# ver_3.net
KiCad netlist of a schematic drawn in Altium Designer
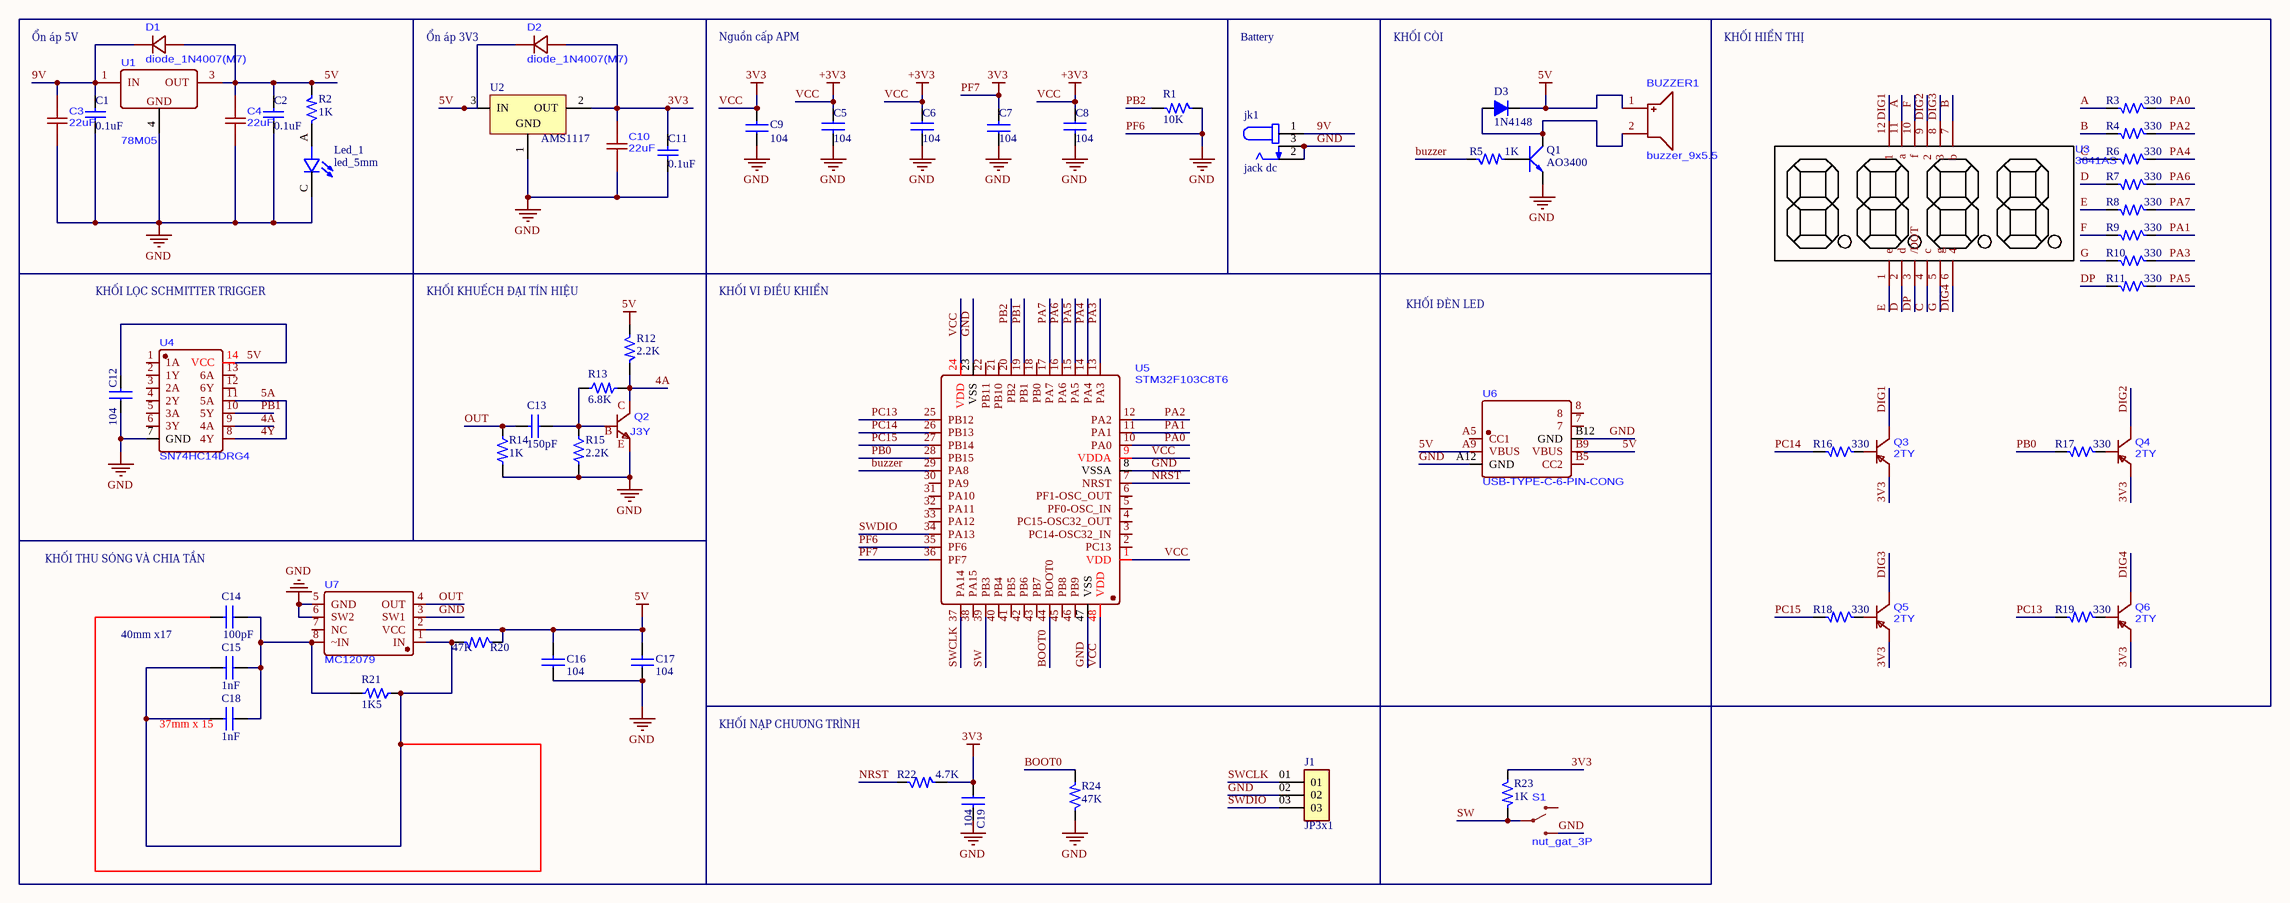
[diagram p0: ver_3.SchDoc]

(export (version "E")
  (design (tool "Eeschema 10.0.6"))
  (components
    (comp (ref "BUZZER1")
      (value "buzzer_9x5.5")
      (footprint "buzzer_9x5.5")
      (libsource (lib "Phong_Cach") (part "buzzer_9x5.5"))
    )
    (comp (ref "C1")
      (value "0.1uF")
      (footprint "CN-SMD-0603")
      (libsource (lib "Thu Vien Chuan MH") (part "CAP 104"))
    )
    (comp (ref "C2")
      (value "0.1uF")
      (footprint "CN-SMD-0603")
      (libsource (lib "Thu Vien Chuan MH") (part "CAP 104"))
    )
    (comp (ref "C3") (value "22uF") (footprint "cap_1206") (libsource (lib "Phong_Cach") (part "cap_1206")))
    (comp (ref "C4") (value "22uF") (footprint "cap_1206") (libsource (lib "Phong_Cach") (part "cap_1206")))
    (comp (ref "C5")
      (value "104")
      (footprint "CN-SMD-0603")
      (description "Tu 0805")
      (libsource (lib "BLE_ST") (part "Tu 0805_1"))
    )
    (comp (ref "C6")
      (value "104")
      (footprint "CN-SMD-0603")
      (description "Tu 0805")
      (libsource (lib "BLE_ST") (part "Tu 0805_1"))
    )
    (comp (ref "C7")
      (value "104")
      (footprint "CN-SMD-0603")
      (description "Tu 0805")
      (libsource (lib "BLE_ST") (part "Tu 0805_1"))
    )
    (comp (ref "C8")
      (value "104")
      (footprint "CN-SMD-0603")
      (description "Tu 0805")
      (libsource (lib "BLE_ST") (part "Tu 0805_1"))
    )
    (comp (ref "C9")
      (value "104")
      (footprint "CN-SMD-0603")
      (description "Tu 0805")
      (libsource (lib "BLE_ST") (part "Tu 0805_1"))
    )
    (comp (ref "C10") (value "22uF") (footprint "cap_1206") (libsource (lib "Phong_Cach") (part "cap_1206")))
    (comp (ref "C11")
      (value "0.1uF")
      (footprint "CN-SMD-0603")
      (libsource (lib "Thu Vien Chuan MH") (part "CAP 104"))
    )
    (comp (ref "C12")
      (value "104")
      (footprint "CN-SMD-0603")
      (description "Tu 0805")
      (libsource (lib "BLE_ST") (part "Tu 0805_1"))
    )
    (comp (ref "C13")
      (value "150pF")
      (footprint "CN-SMD-0603")
      (description "Tu 0805")
      (libsource (lib "BLE_ST") (part "Tu 0805_1"))
    )
    (comp (ref "C14")
      (value "100pF")
      (footprint "CN-SMD-0603")
      (description "Tu 0805")
      (libsource (lib "BLE_ST") (part "Tu 0805_1"))
    )
    (comp (ref "C15")
      (value "1nF")
      (footprint "CN-SMD-0603")
      (description "Tu 0805")
      (libsource (lib "BLE_ST") (part "Tu 0805_1"))
    )
    (comp (ref "C16")
      (value "104")
      (footprint "CN-SMD-0603")
      (description "Tu 0805")
      (libsource (lib "BLE_ST") (part "Tu 0805_1"))
    )
    (comp (ref "C17")
      (value "104")
      (footprint "CN-SMD-0603")
      (description "Tu 0805")
      (libsource (lib "BLE_ST") (part "Tu 0805_1"))
    )
    (comp (ref "C18")
      (value "1nF")
      (footprint "CN-SMD-0603")
      (description "Tu 0805")
      (libsource (lib "BLE_ST") (part "Tu 0805_1"))
    )
    (comp (ref "C19")
      (value "104")
      (footprint "CN-SMD-0603")
      (description "Tu 0805")
      (libsource (lib "BLE_ST") (part "Tu 0805_1"))
    )
    (comp (ref "D1")
      (value "diode_1N4007(M7)")
      (footprint "diode_1N4007-M7")
      (libsource (lib "Phong_Cach") (part "diode_1N4007(M7)"))
    )
    (comp (ref "D2")
      (value "diode_1N4007(M7)")
      (footprint "diode_1N4007-M7")
      (libsource (lib "Phong_Cach") (part "diode_1N4007(M7)"))
    )
    (comp (ref "D3")
      (value "1N4148")
      (footprint "SOD-123")
      (description "Diode 1A")
      (libsource (lib "syhaunguyen") (part "D1A"))
    )
    (comp (ref "J1") (value "JP3x1") (footprint "JP3x1") (libsource (lib "Phong_Cach") (part "JP3x1")))
    (comp (ref "jk1") (value "jack dc") (footprint "jack dc") (libsource (lib "Phong_Cach") (part "jack dc")))
    (comp (ref "Led_1")
      (value "led_5mm")
      (footprint "led_5mm")
      (libsource (lib "Phong_Cach") (part "led_5mm"))
    )
    (comp (ref "Q1")
      (value "AO3400")
      (footprint "SOT23B")
      (description "NPN 600mW, ECB")
      (libsource (lib "BLE_ST") (part "C1815"))
    )
    (comp (ref "Q2") (value "J3Y") (footprint "j3y") (libsource (lib "Phong_Cach") (part "S8050/J3Y/0.4")))
    (comp (ref "Q3") (value "2TY") (footprint "2TY") (libsource (lib "Phong_Cach") (part "2TY")))
    (comp (ref "Q4") (value "2TY") (footprint "2TY") (libsource (lib "Phong_Cach") (part "2TY")))
    (comp (ref "Q5") (value "2TY") (footprint "2TY") (libsource (lib "Phong_Cach") (part "2TY")))
    (comp (ref "Q6") (value "2TY") (footprint "2TY") (libsource (lib "Phong_Cach") (part "2TY")))
    (comp (ref "R1")
      (value "10K")
      (footprint "RES-SMD-0603")
      (description "Tro 0805")
      (libsource (lib "BLE_ST") (part "Tro 0805_1"))
    )
    (comp (ref "R2")
      (value "1K")
      (footprint "RES-SMD-0603")
      (description "Resistor 1/4W")
      (libsource (lib "BLE_ST") (part "Res"))
    )
    (comp (ref "R3")
      (value "330")
      (footprint "RES-SMD-0603")
      (description "Resistor 1/4W")
      (libsource (lib "BLE_ST") (part "Res"))
    )
    (comp (ref "R4")
      (value "330")
      (footprint "RES-SMD-0603")
      (description "Resistor 1/4W")
      (libsource (lib "BLE_ST") (part "Res"))
    )
    (comp (ref "R5")
      (value "1K")
      (footprint "RES-SMD-0603")
      (description "Resistor 1/4W")
      (libsource (lib "Lib_Chuan_03_08_2013") (part "Res"))
    )
    (comp (ref "R6")
      (value "330")
      (footprint "RES-SMD-0603")
      (description "Resistor 1/4W")
      (libsource (lib "BLE_ST") (part "Res"))
    )
    (comp (ref "R7")
      (value "330")
      (footprint "RES-SMD-0603")
      (description "Resistor 1/4W")
      (libsource (lib "BLE_ST") (part "Res"))
    )
    (comp (ref "R8")
      (value "330")
      (footprint "RES-SMD-0603")
      (description "Resistor 1/4W")
      (libsource (lib "BLE_ST") (part "Res"))
    )
    (comp (ref "R9")
      (value "330")
      (footprint "RES-SMD-0603")
      (description "Resistor 1/4W")
      (libsource (lib "BLE_ST") (part "Res"))
    )
    (comp (ref "R10")
      (value "330")
      (footprint "RES-SMD-0603")
      (description "Resistor 1/4W")
      (libsource (lib "BLE_ST") (part "Res"))
    )
    (comp (ref "R11")
      (value "330")
      (footprint "RES-SMD-0603")
      (description "Resistor 1/4W")
      (libsource (lib "BLE_ST") (part "Res"))
    )
    (comp (ref "R12")
      (value "2.2K")
      (footprint "RES-SMD-0603")
      (description "Tro 0805")
      (libsource (lib "BLE_ST") (part "Tro 0805_1"))
    )
    (comp (ref "R13")
      (value "6.8K")
      (footprint "RES-SMD-0603")
      (description "Tro 0805")
      (libsource (lib "BLE_ST") (part "Tro 0805_1"))
    )
    (comp (ref "R14")
      (value "1K")
      (footprint "RES-SMD-0603")
      (description "Tro 0805")
      (libsource (lib "BLE_ST") (part "Tro 0805_1"))
    )
    (comp (ref "R15")
      (value "2.2K")
      (footprint "RES-SMD-0603")
      (description "Tro 0805")
      (libsource (lib "BLE_ST") (part "Tro 0805_1"))
    )
    (comp (ref "R16")
      (value "330")
      (footprint "RES-SMD-0603")
      (description "Resistor 1/4W")
      (libsource (lib "BLE_ST") (part "Res"))
    )
    (comp (ref "R17")
      (value "330")
      (footprint "RES-SMD-0603")
      (description "Resistor 1/4W")
      (libsource (lib "BLE_ST") (part "Res"))
    )
    (comp (ref "R18")
      (value "330")
      (footprint "RES-SMD-0603")
      (description "Resistor 1/4W")
      (libsource (lib "BLE_ST") (part "Res"))
    )
    (comp (ref "R19")
      (value "330")
      (footprint "RES-SMD-0603")
      (description "Resistor 1/4W")
      (libsource (lib "BLE_ST") (part "Res"))
    )
    (comp (ref "R20")
      (value "47K")
      (footprint "RES-SMD-0603")
      (description "Tro 0805")
      (libsource (lib "BLE_ST") (part "Tro 0805_1"))
    )
    (comp (ref "R21")
      (value "1K5")
      (footprint "RES-SMD-0603")
      (description "Tro 0805")
      (libsource (lib "BLE_ST") (part "Tro 0805_1"))
    )
    (comp (ref "R22")
      (value "4.7K")
      (footprint "RES-SMD-0603")
      (description "Tro 0805")
      (libsource (lib "BLE_ST") (part "Tro 0805_1"))
    )
    (comp (ref "R23")
      (value "1K")
      (footprint "RES-SMD-0603")
      (description "Tro 0805")
      (libsource (lib "BLE_ST") (part "Tro 0805_1"))
    )
    (comp (ref "R24")
      (value "47K")
      (footprint "RES-SMD-0603")
      (description "Tro 0805")
      (libsource (lib "BLE_ST") (part "Tro 0805_1"))
    )
    (comp (ref "S1")
      (value "nut_gat_3P")
      (footprint "nut_gat_3p")
      (libsource (lib "Phong_Cach") (part "nut_gat_3P"))
    )
    (comp (ref "U1") (value "78M05") (footprint "78M05") (libsource (lib "Phong_Cach") (part "78M05")))
    (comp (ref "U2")
      (value "AMS1117")
      (footprint "AMS1117-SOT223")
      (libsource (lib "QT TECH CO.,LTD") (part "AMS1117"))
    )
    (comp (ref "U3") (value "3641AS") (footprint "3641BS") (libsource (lib "Phong_Cach") (part "3641AS")))
    (comp (ref "U4")
      (value "SN74HC14DRG4")
      (footprint "74HC14")
      (libsource (lib "Phong_Cach") (part "SN74HC14DRG4"))
    )
    (comp (ref "U5")
      (value "STM32F103C8T6")
      (footprint "LQFP-48_L7.0-W7.0-P0.50-LS9.0-BL")
      (libsource (lib "Phong_Cach") (part "APM32F030C8T6"))
    )
    (comp (ref "U6")
      (value "USB-TYPE-C-6-PIN-CONG")
      (footprint "USB-TYPE-C-6-PIN-CONG")
      (libsource (lib "Phong_Cach") (part "USB-TYPE-C-6-PIN-CONG"))
    )
    (comp (ref "U7") (value "MC12079") (footprint "MC12079") (libsource (lib "Phong_Cach") (part "MC12079")))
  )
  (nets
    (net (code "1") (name "+3V3") (class "Default")
      (node (ref "C10") (pin "2") (pinfunction "2_2") (pintype "passive"))
      (node (ref "C11") (pin "2") (pinfunction "2_2") (pintype "passive"))
      (node (ref "C19") (pin "1") (pinfunction "1_1") (pintype "passive"))
      (node (ref "C5") (pin "1") (pinfunction "1_1") (pintype "passive"))
      (node (ref "C6") (pin "1") (pinfunction "1_1") (pintype "passive"))
      (node (ref "C7") (pin "2") (pinfunction "2_2") (pintype "passive"))
      (node (ref "C8") (pin "1") (pinfunction "1_1") (pintype "passive"))
      (node (ref "C9") (pin "2") (pinfunction "2_2") (pintype "passive"))
      (node (ref "D2") (pin "2") (pinfunction "A_2") (pintype "passive"))
      (node (ref "Q3") (pin "2") (pinfunction "E_2") (pintype "passive"))
      (node (ref "Q4") (pin "2") (pinfunction "E_2") (pintype "passive"))
      (node (ref "Q5") (pin "2") (pinfunction "E_2") (pintype "passive"))
      (node (ref "Q6") (pin "2") (pinfunction "E_2") (pintype "passive"))
      (node (ref "R22") (pin "2") (pinfunction "2_2") (pintype "passive"))
      (node (ref "R23") (pin "1") (pinfunction "1_1") (pintype "passive"))
      (node (ref "U2") (pin "2") (pinfunction "OUT_2") (pintype "power_in"))
      (node (ref "U5") (pin "1") (pinfunction "VDD_1") (pintype "passive"))
      (node (ref "U5") (pin "24") (pinfunction "VDD_24") (pintype "passive"))
      (node (ref "U5") (pin "36") (pinfunction "PF7_36") (pintype "passive"))
      (node (ref "U5") (pin "48") (pinfunction "VDD_48") (pintype "passive"))
      (node (ref "U5") (pin "9") (pinfunction "VDDA_9") (pintype "passive"))
    )
    (net (code "2") (name "/4A") (class "Default")
      (node (ref "Q2") (pin "3") (pinfunction "C_3") (pintype "passive"))
      (node (ref "R12") (pin "2") (pinfunction "2_2") (pintype "passive"))
      (node (ref "R13") (pin "2") (pinfunction "2_2") (pintype "passive"))
      (node (ref "U4") (pin "9") (pinfunction "4A_9") (pintype "passive"))
    )
    (net (code "3") (name "/4Y") (class "Default")
      (node (ref "U4") (pin "11") (pinfunction "5A_11") (pintype "passive"))
      (node (ref "U4") (pin "8") (pinfunction "4Y_8") (pintype "passive"))
    )
    (net (code "4") (name "/9V") (class "Default")
      (node (ref "C1") (pin "2") (pinfunction "2_2") (pintype "passive"))
      (node (ref "C3") (pin "2") (pinfunction "2_2") (pintype "passive"))
      (node (ref "D1") (pin "1") (pinfunction "K_1") (pintype "passive"))
      (node (ref "U1") (pin "1") (pinfunction "IN_1") (pintype "passive"))
      (node (ref "jk1") (pin "1") (pinfunction "1_1") (pintype "passive"))
    )
    (net (code "5") (name "/A") (class "Default")
      (node (ref "R3") (pin "2") (pinfunction "2_2") (pintype "passive"))
      (node (ref "U3") (pin "11") (pinfunction "a_11") (pintype "passive"))
    )
    (net (code "6") (name "/B") (class "Default")
      (node (ref "R4") (pin "2") (pinfunction "2_2") (pintype "passive"))
      (node (ref "U3") (pin "7") (pinfunction "b_7") (pintype "passive"))
    )
    (net (code "7") (name "/BOOT0") (class "Default")
      (node (ref "R24") (pin "2") (pinfunction "2_2") (pintype "passive"))
      (node (ref "U5") (pin "44") (pinfunction "BOOT0_44") (pintype "passive"))
    )
    (net (code "8") (name "/C") (class "Default")
      (node (ref "R6") (pin "2") (pinfunction "2_2") (pintype "passive"))
      (node (ref "U3") (pin "4") (pinfunction "c_4") (pintype "passive"))
    )
    (net (code "9") (name "/D") (class "Default")
      (node (ref "R7") (pin "2") (pinfunction "2_2") (pintype "passive"))
      (node (ref "U3") (pin "2") (pinfunction "d_2") (pintype "passive"))
    )
    (net (code "10") (name "/DIG1") (class "Default")
      (node (ref "Q3") (pin "3") (pinfunction "C_3") (pintype "passive"))
      (node (ref "U3") (pin "12") (pinfunction "1_12") (pintype "passive"))
    )
    (net (code "11") (name "/DIG2") (class "Default")
      (node (ref "Q4") (pin "3") (pinfunction "C_3") (pintype "passive"))
      (node (ref "U3") (pin "9") (pinfunction "2_9") (pintype "passive"))
    )
    (net (code "12") (name "/DIG3") (class "Default")
      (node (ref "Q5") (pin "3") (pinfunction "C_3") (pintype "passive"))
      (node (ref "U3") (pin "8") (pinfunction "3_8") (pintype "passive"))
    )
    (net (code "13") (name "/DIG4") (class "Default")
      (node (ref "Q6") (pin "3") (pinfunction "C_3") (pintype "passive"))
      (node (ref "U3") (pin "6") (pinfunction "4_6") (pintype "passive"))
    )
    (net (code "14") (name "/DP") (class "Default")
      (node (ref "R11") (pin "2") (pinfunction "2_2") (pintype "passive"))
      (node (ref "U3") (pin "3") (pinfunction "/DOT_3") (pintype "passive"))
    )
    (net (code "15") (name "/E") (class "Default")
      (node (ref "R8") (pin "2") (pinfunction "2_2") (pintype "passive"))
      (node (ref "U3") (pin "1") (pinfunction "e_1") (pintype "passive"))
    )
    (net (code "16") (name "/F") (class "Default")
      (node (ref "R9") (pin "2") (pinfunction "2_2") (pintype "passive"))
      (node (ref "U3") (pin "10") (pinfunction "f_10") (pintype "passive"))
    )
    (net (code "17") (name "/G") (class "Default")
      (node (ref "R10") (pin "2") (pinfunction "2_2") (pintype "passive"))
      (node (ref "U3") (pin "5") (pinfunction "g_5") (pintype "passive"))
    )
    (net (code "18") (name "/NRST") (class "Default")
      (node (ref "R22") (pin "1") (pinfunction "1_1") (pintype "passive"))
      (node (ref "U5") (pin "7") (pinfunction "NRST_7") (pintype "passive"))
    )
    (net (code "19") (name "/OUT") (class "Default")
      (node (ref "C13") (pin "2") (pinfunction "2_2") (pintype "passive"))
      (node (ref "R14") (pin "1") (pinfunction "1_1") (pintype "passive"))
      (node (ref "U7") (pin "4") (pinfunction "OUT_4") (pintype "passive"))
    )
    (net (code "20") (name "/PA0") (class "Default")
      (node (ref "R3") (pin "1") (pinfunction "1_1") (pintype "passive"))
      (node (ref "U5") (pin "10") (pinfunction "PA0_10") (pintype "passive"))
    )
    (net (code "21") (name "/PA1") (class "Default")
      (node (ref "R9") (pin "1") (pinfunction "1_1") (pintype "passive"))
      (node (ref "U5") (pin "11") (pinfunction "PA1_11") (pintype "passive"))
    )
    (net (code "22") (name "/PA2") (class "Default")
      (node (ref "R4") (pin "1") (pinfunction "1_1") (pintype "passive"))
      (node (ref "U5") (pin "12") (pinfunction "PA2_12") (pintype "passive"))
    )
    (net (code "23") (name "/PA3") (class "Default")
      (node (ref "R10") (pin "1") (pinfunction "1_1") (pintype "passive"))
      (node (ref "U5") (pin "13") (pinfunction "PA3_13") (pintype "passive"))
    )
    (net (code "24") (name "/PA4") (class "Default")
      (node (ref "R6") (pin "1") (pinfunction "1_1") (pintype "passive"))
      (node (ref "U5") (pin "14") (pinfunction "PA4_14") (pintype "passive"))
    )
    (net (code "25") (name "/PA5") (class "Default")
      (node (ref "R11") (pin "1") (pinfunction "1_1") (pintype "passive"))
      (node (ref "U5") (pin "15") (pinfunction "PA5_15") (pintype "passive"))
    )
    (net (code "26") (name "/PA6") (class "Default")
      (node (ref "R7") (pin "1") (pinfunction "1_1") (pintype "passive"))
      (node (ref "U5") (pin "16") (pinfunction "PA6_16") (pintype "passive"))
    )
    (net (code "27") (name "/PA7") (class "Default")
      (node (ref "R8") (pin "1") (pinfunction "1_1") (pintype "passive"))
      (node (ref "U5") (pin "17") (pinfunction "PA7_17") (pintype "passive"))
    )
    (net (code "28") (name "/PB0") (class "Default")
      (node (ref "R17") (pin "2") (pinfunction "2_2") (pintype "passive"))
      (node (ref "U5") (pin "28") (pinfunction "PB15_28") (pintype "passive"))
    )
    (net (code "29") (name "/PB1") (class "Default")
      (node (ref "U4") (pin "10") (pinfunction "5Y_10") (pintype "passive"))
      (node (ref "U5") (pin "19") (pinfunction "PB1_19") (pintype "passive"))
    )
    (net (code "30") (name "/PB2") (class "Default")
      (node (ref "R1") (pin "2") (pinfunction "2_2") (pintype "passive"))
      (node (ref "U5") (pin "20") (pinfunction "PB2_20") (pintype "passive"))
    )
    (net (code "31") (name "/PC13") (class "Default")
      (node (ref "R19") (pin "2") (pinfunction "2_2") (pintype "passive"))
      (node (ref "U5") (pin "25") (pinfunction "PB12_25") (pintype "passive"))
    )
    (net (code "32") (name "/PC14") (class "Default")
      (node (ref "R16") (pin "2") (pinfunction "2_2") (pintype "passive"))
      (node (ref "U5") (pin "26") (pinfunction "PB13_26") (pintype "passive"))
    )
    (net (code "33") (name "/PC15") (class "Default")
      (node (ref "R18") (pin "2") (pinfunction "2_2") (pintype "passive"))
      (node (ref "U5") (pin "27") (pinfunction "PB14_27") (pintype "passive"))
    )
    (net (code "34") (name "/SW") (class "Default")
      (node (ref "R23") (pin "2") (pinfunction "2_2") (pintype "passive"))
      (node (ref "S1") (pin "2") (pinfunction "P_2") (pintype "passive"))
      (node (ref "U5") (pin "39") (pinfunction "PB3_39") (pintype "passive"))
    )
    (net (code "35") (name "/SWCLK") (class "Default")
      (node (ref "J1") (pin "01") (pinfunction "01_01") (pintype "passive"))
      (node (ref "U5") (pin "37") (pinfunction "PA14_37") (pintype "passive"))
    )
    (net (code "36") (name "/SWDIO") (class "Default")
      (node (ref "J1") (pin "03") (pinfunction "03_03") (pintype "passive"))
      (node (ref "U5") (pin "34") (pinfunction "PA13_34") (pintype "passive"))
    )
    (net (code "37") (name "/buzzer") (class "Default")
      (node (ref "R5") (pin "1") (pinfunction "1_1") (pintype "passive"))
      (node (ref "U5") (pin "29") (pinfunction "PA8_29") (pintype "passive"))
    )
    (net (code "38") (name "5V") (class "Default")
      (node (ref "BUZZER1") (pin "1") (pinfunction "1_1") (pintype "passive"))
      (node (ref "C12") (pin "2") (pinfunction "2_2") (pintype "passive"))
      (node (ref "C16") (pin "2") (pinfunction "2_2") (pintype "passive"))
      (node (ref "C17") (pin "2") (pinfunction "2_2") (pintype "passive"))
      (node (ref "C2") (pin "2") (pinfunction "2_2") (pintype "passive"))
      (node (ref "C4") (pin "2") (pinfunction "2_2") (pintype "passive"))
      (node (ref "D1") (pin "2") (pinfunction "A_2") (pintype "passive"))
      (node (ref "D2") (pin "1") (pinfunction "K_1") (pintype "passive"))
      (node (ref "D3") (pin "2") (pinfunction "K_2") (pintype "passive"))
      (node (ref "R12") (pin "1") (pinfunction "1_1") (pintype "passive"))
      (node (ref "R2") (pin "2") (pinfunction "2_2") (pintype "passive"))
      (node (ref "R20") (pin "1") (pinfunction "1_1") (pintype "passive"))
      (node (ref "U1") (pin "3") (pinfunction "OUT_3") (pintype "passive"))
      (node (ref "U2") (pin "3") (pinfunction "IN_3") (pintype "power_in"))
      (node (ref "U4") (pin "14") (pinfunction "VCC_14") (pintype "passive"))
      (node (ref "U6") (pin "A9") (pinfunction "VBUS_A9") (pintype "passive"))
      (node (ref "U6") (pin "B9") (pinfunction "VBUS_B9") (pintype "passive"))
      (node (ref "U7") (pin "2") (pinfunction "VCC_2") (pintype "passive"))
    )
    (net (code "39") (name "GND") (class "Default")
      (node (ref "C1") (pin "1") (pinfunction "1_1") (pintype "passive"))
      (node (ref "C10") (pin "1") (pinfunction "1_1") (pintype "passive"))
      (node (ref "C11") (pin "1") (pinfunction "1_1") (pintype "passive"))
      (node (ref "C12") (pin "1") (pinfunction "1_1") (pintype "passive"))
      (node (ref "C16") (pin "1") (pinfunction "1_1") (pintype "passive"))
      (node (ref "C17") (pin "1") (pinfunction "1_1") (pintype "passive"))
      (node (ref "C19") (pin "2") (pinfunction "2_2") (pintype "passive"))
      (node (ref "C2") (pin "1") (pinfunction "1_1") (pintype "passive"))
      (node (ref "C3") (pin "1") (pinfunction "1_1") (pintype "passive"))
      (node (ref "C4") (pin "1") (pinfunction "1_1") (pintype "passive"))
      (node (ref "C5") (pin "2") (pinfunction "2_2") (pintype "passive"))
      (node (ref "C6") (pin "2") (pinfunction "2_2") (pintype "passive"))
      (node (ref "C7") (pin "1") (pinfunction "1_1") (pintype "passive"))
      (node (ref "C8") (pin "2") (pinfunction "2_2") (pintype "passive"))
      (node (ref "C9") (pin "1") (pinfunction "1_1") (pintype "passive"))
      (node (ref "J1") (pin "02") (pinfunction "02_02") (pintype "passive"))
      (node (ref "Led_1") (pin "C") (pinfunction "C_C") (pintype "passive"))
      (node (ref "Q1") (pin "1") (pinfunction "E_1") (pintype "passive"))
      (node (ref "Q2") (pin "2") (pinfunction "E_2") (pintype "passive"))
      (node (ref "R1") (pin "1") (pinfunction "1_1") (pintype "passive"))
      (node (ref "R14") (pin "2") (pinfunction "2_2") (pintype "passive"))
      (node (ref "R15") (pin "2") (pinfunction "2_2") (pintype "passive"))
      (node (ref "R24") (pin "1") (pinfunction "1_1") (pintype "passive"))
      (node (ref "S1") (pin "3") (pinfunction "S_3") (pintype "passive"))
      (node (ref "U1") (pin "4") (pinfunction "GND_4") (pintype "passive"))
      (node (ref "U2") (pin "1") (pinfunction "GND_1") (pintype "power_in"))
      (node (ref "U4") (pin "7") (pinfunction "GND_7") (pintype "passive"))
      (node (ref "U5") (pin "23") (pinfunction "VSS_23") (pintype "passive"))
      (node (ref "U5") (pin "35") (pinfunction "PF6_35") (pintype "passive"))
      (node (ref "U5") (pin "47") (pinfunction "VSS_47") (pintype "passive"))
      (node (ref "U5") (pin "8") (pinfunction "VSSA_8") (pintype "passive"))
      (node (ref "U6") (pin "A12") (pinfunction "GND_A12") (pintype "passive"))
      (node (ref "U6") (pin "B12") (pinfunction "GND_B12") (pintype "passive"))
      (node (ref "U7") (pin "3") (pinfunction "SW1_3") (pintype "passive"))
      (node (ref "U7") (pin "5") (pinfunction "GND_5") (pintype "passive"))
      (node (ref "U7") (pin "6") (pinfunction "SW2_6") (pintype "passive"))
      (node (ref "jk1") (pin "2") (pinfunction "2_2") (pintype "passive"))
      (node (ref "jk1") (pin "3") (pinfunction "3_3") (pintype "passive"))
    )
    (net (code "40") (name "Net-(D3-A)") (class "Default")
      (node (ref "BUZZER1") (pin "2") (pinfunction "2_2") (pintype "passive"))
      (node (ref "D3") (pin "1") (pinfunction "A_1") (pintype "passive"))
      (node (ref "Q1") (pin "2") (pinfunction "C_2") (pintype "passive"))
    )
    (net (code "41") (name "Net-(Led_1-PadA)") (class "Default")
      (node (ref "Led_1") (pin "A") (pinfunction "A_A") (pintype "passive"))
      (node (ref "R2") (pin "1") (pinfunction "1_1") (pintype "passive"))
    )
    (net (code "42") (name "Net-(Q1-B)") (class "Default")
      (node (ref "Q1") (pin "3") (pinfunction "B_3") (pintype "passive"))
      (node (ref "R5") (pin "2") (pinfunction "2_2") (pintype "passive"))
    )
    (net (code "43") (name "Net-(Q2-B)") (class "Default")
      (node (ref "C13") (pin "1") (pinfunction "1_1") (pintype "passive"))
      (node (ref "Q2") (pin "1") (pinfunction "B_1") (pintype "passive"))
      (node (ref "R13") (pin "1") (pinfunction "1_1") (pintype "passive"))
      (node (ref "R15") (pin "1") (pinfunction "1_1") (pintype "passive"))
    )
    (net (code "44") (name "Net-(Q3-B)") (class "Default")
      (node (ref "Q3") (pin "1") (pinfunction "B_1") (pintype "passive"))
      (node (ref "R16") (pin "1") (pinfunction "1_1") (pintype "passive"))
    )
    (net (code "45") (name "Net-(Q4-B)") (class "Default")
      (node (ref "Q4") (pin "1") (pinfunction "B_1") (pintype "passive"))
      (node (ref "R17") (pin "1") (pinfunction "1_1") (pintype "passive"))
    )
    (net (code "46") (name "Net-(Q5-B)") (class "Default")
      (node (ref "Q5") (pin "1") (pinfunction "B_1") (pintype "passive"))
      (node (ref "R18") (pin "1") (pinfunction "1_1") (pintype "passive"))
    )
    (net (code "47") (name "Net-(Q6-B)") (class "Default")
      (node (ref "Q6") (pin "1") (pinfunction "B_1") (pintype "passive"))
      (node (ref "R19") (pin "1") (pinfunction "1_1") (pintype "passive"))
    )
    (net (code "48") (name "Net-(U7-IN)") (class "Default")
      (node (ref "C14") (pin "2") (pinfunction "2_2") (pintype "passive"))
      (node (ref "C15") (pin "2") (pinfunction "2_2") (pintype "passive"))
      (node (ref "C18") (pin "2") (pinfunction "2_2") (pintype "passive"))
      (node (ref "R20") (pin "2") (pinfunction "2_2") (pintype "passive"))
      (node (ref "R21") (pin "1") (pinfunction "1_1") (pintype "passive"))
      (node (ref "U7") (pin "1") (pinfunction "IN_1") (pintype "passive"))
    )
    (net (code "49") (name "Net-(U7-~IN)") (class "Default")
      (node (ref "C14") (pin "1") (pinfunction "1_1") (pintype "passive"))
      (node (ref "C15") (pin "1") (pinfunction "1_1") (pintype "passive"))
      (node (ref "C18") (pin "1") (pinfunction "1_1") (pintype "passive"))
      (node (ref "R21") (pin "2") (pinfunction "2_2") (pintype "passive"))
      (node (ref "U7") (pin "8") (pinfunction "~IN_8") (pintype "passive"))
    )
    (net (code "50") (name "unconnected-(S1-O-Pad1)") (class "Default")
      (node (ref "S1") (pin "1") (pinfunction "O_1") (pintype "passive"))
    )
    (net (code "51") (name "unconnected-(U4-1A-Pad1)") (class "Default")
      (node (ref "U4") (pin "1") (pinfunction "1A_1") (pintype "passive"))
    )
    (net (code "52") (name "unconnected-(U4-1Y-Pad2)") (class "Default")
      (node (ref "U4") (pin "2") (pinfunction "1Y_2") (pintype "passive"))
    )
    (net (code "53") (name "unconnected-(U4-2A-Pad3)") (class "Default")
      (node (ref "U4") (pin "3") (pinfunction "2A_3") (pintype "passive"))
    )
    (net (code "54") (name "unconnected-(U4-2Y-Pad4)") (class "Default")
      (node (ref "U4") (pin "4") (pinfunction "2Y_4") (pintype "passive"))
    )
    (net (code "55") (name "unconnected-(U4-3A-Pad5)") (class "Default")
      (node (ref "U4") (pin "5") (pinfunction "3A_5") (pintype "passive"))
    )
    (net (code "56") (name "unconnected-(U4-3Y-Pad6)") (class "Default")
      (node (ref "U4") (pin "6") (pinfunction "3Y_6") (pintype "passive"))
    )
    (net (code "57") (name "unconnected-(U4-6A-Pad13)") (class "Default")
      (node (ref "U4") (pin "13") (pinfunction "6A_13") (pintype "passive"))
    )
    (net (code "58") (name "unconnected-(U4-6Y-Pad12)") (class "Default")
      (node (ref "U4") (pin "12") (pinfunction "6Y_12") (pintype "passive"))
    )
    (net (code "59") (name "unconnected-(U5-PA9-Pad30)") (class "Default")
      (node (ref "U5") (pin "30") (pinfunction "PA9_30") (pintype "passive"))
    )
    (net (code "60") (name "unconnected-(U5-PA10-Pad31)") (class "Default")
      (node (ref "U5") (pin "31") (pinfunction "PA10_31") (pintype "passive"))
    )
    (net (code "61") (name "unconnected-(U5-PA11-Pad32)") (class "Default")
      (node (ref "U5") (pin "32") (pinfunction "PA11_32") (pintype "passive"))
    )
    (net (code "62") (name "unconnected-(U5-PA12-Pad33)") (class "Default")
      (node (ref "U5") (pin "33") (pinfunction "PA12_33") (pintype "passive"))
    )
    (net (code "63") (name "unconnected-(U5-PA15-Pad38)") (class "Default")
      (node (ref "U5") (pin "38") (pinfunction "PA15_38") (pintype "passive"))
    )
    (net (code "64") (name "unconnected-(U5-PB0-Pad18)") (class "Default")
      (node (ref "U5") (pin "18") (pinfunction "PB0_18") (pintype "passive"))
    )
    (net (code "65") (name "unconnected-(U5-PB4-Pad40)") (class "Default")
      (node (ref "U5") (pin "40") (pinfunction "PB4_40") (pintype "passive"))
    )
    (net (code "66") (name "unconnected-(U5-PB5-Pad41)") (class "Default")
      (node (ref "U5") (pin "41") (pinfunction "PB5_41") (pintype "passive"))
    )
    (net (code "67") (name "unconnected-(U5-PB6-Pad42)") (class "Default")
      (node (ref "U5") (pin "42") (pinfunction "PB6_42") (pintype "passive"))
    )
    (net (code "68") (name "unconnected-(U5-PB7-Pad43)") (class "Default")
      (node (ref "U5") (pin "43") (pinfunction "PB7_43") (pintype "passive"))
    )
    (net (code "69") (name "unconnected-(U5-PB8-Pad45)") (class "Default")
      (node (ref "U5") (pin "45") (pinfunction "PB8_45") (pintype "passive"))
    )
    (net (code "70") (name "unconnected-(U5-PB9-Pad46)") (class "Default")
      (node (ref "U5") (pin "46") (pinfunction "PB9_46") (pintype "passive"))
    )
    (net (code "71") (name "unconnected-(U5-PB10-Pad21)") (class "Default")
      (node (ref "U5") (pin "21") (pinfunction "PB10_21") (pintype "passive"))
    )
    (net (code "72") (name "unconnected-(U5-PB11-Pad22)") (class "Default")
      (node (ref "U5") (pin "22") (pinfunction "PB11_22") (pintype "passive"))
    )
    (net (code "73") (name "unconnected-(U5-PC13-Pad2)") (class "Default")
      (node (ref "U5") (pin "2") (pinfunction "PC13_2") (pintype "passive"))
    )
    (net (code "74") (name "unconnected-(U5-PC14-OSC32_IN-Pad3)") (class "Default")
      (node (ref "U5") (pin "3") (pinfunction "PC14-OSC32_IN_3") (pintype "passive"))
    )
    (net (code "75") (name "unconnected-(U5-PC15-OSC32_OUT-Pad4)") (class "Default")
      (node (ref "U5") (pin "4") (pinfunction "PC15-OSC32_OUT_4") (pintype "passive"))
    )
    (net (code "76") (name "unconnected-(U5-PF0-OSC_IN-Pad5)") (class "Default")
      (node (ref "U5") (pin "5") (pinfunction "PF0-OSC_IN_5") (pintype "passive"))
    )
    (net (code "77") (name "unconnected-(U5-PF1-OSC_OUT-Pad6)") (class "Default")
      (node (ref "U5") (pin "6") (pinfunction "PF1-OSC_OUT_6") (pintype "passive"))
    )
    (net (code "78") (name "unconnected-(U6-CC1-PadA5)") (class "Default")
      (node (ref "U6") (pin "A5") (pinfunction "CC1_A5") (pintype "passive"))
    )
    (net (code "79") (name "unconnected-(U6-CC2-PadB5)") (class "Default")
      (node (ref "U6") (pin "B5") (pinfunction "CC2_B5") (pintype "passive"))
    )
    (net (code "80") (name "unconnected-(U6-Pad7)") (class "Default")
      (node (ref "U6") (pin "7") (pinfunction "7_7") (pintype "passive"))
    )
    (net (code "81") (name "unconnected-(U6-Pad8)") (class "Default")
      (node (ref "U6") (pin "8") (pinfunction "8_8") (pintype "passive"))
    )
    (net (code "82") (name "unconnected-(U7-NC-Pad7)") (class "Default")
      (node (ref "U7") (pin "7") (pinfunction "NC_7") (pintype "passive"))
    )
  )
)
